# mp28164-buck-boost-flashlight-driver-tes.net
KiCad netlist of a schematic drawn in EAGLE
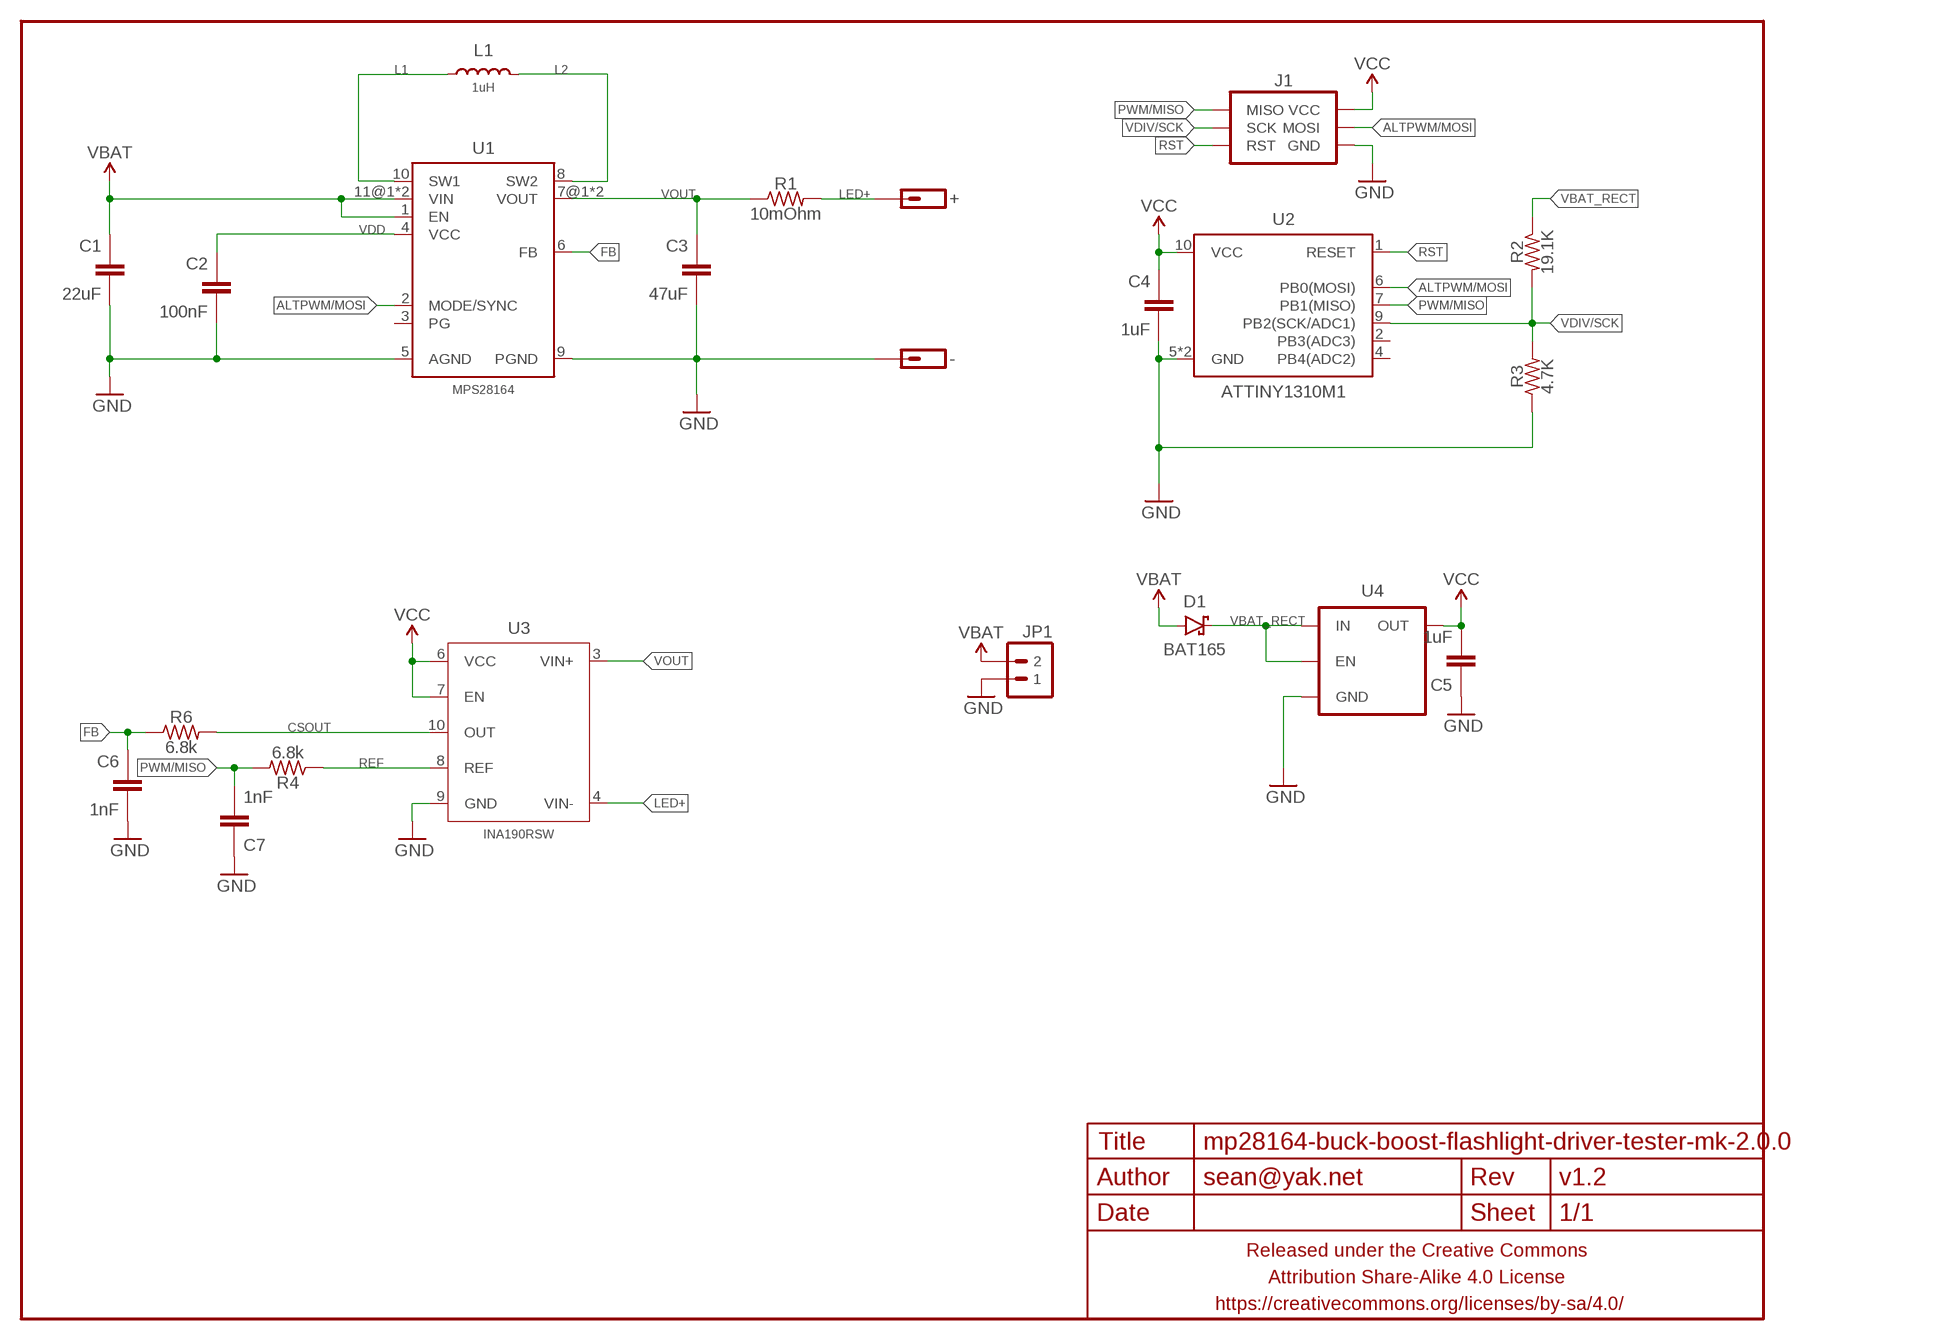
[diagram p0: schematic, sheet 1]

(export (version "E")
  (design (tool "Eeschema 10.0.6"))
  (components
    (comp (ref "+")
      (value "M01PTH-1.2MM-NS")
      (footprint "eagle-import:1X01-1.2MM-NS")
      (libsource (lib "eagle-import") (part "M01PTH-1.2MM-NS"))
    )
    (comp (ref "-")
      (value "M01PTH-1.2MM-NS")
      (footprint "eagle-import:1X01-1.2MM-NS")
      (libsource (lib "eagle-import") (part "M01PTH-1.2MM-NS"))
    )
    (comp (ref "C1")
      (value "22uF")
      (footprint "eagle-import:C1206")
      (libsource (lib "eagle-import") (part "CAPACITOR-CERAMICC1206"))
    )
    (comp (ref "C2")
      (value "100nF")
      (footprint "eagle-import:C0402")
      (libsource (lib "eagle-import") (part "CAPACITOR-CERAMICC0402"))
    )
    (comp (ref "C3")
      (value "47uF")
      (footprint "eagle-import:C1206")
      (libsource (lib "eagle-import") (part "CAPACITOR-CERAMICC1206"))
    )
    (comp (ref "C4")
      (value "1uF")
      (footprint "eagle-import:C0402")
      (libsource (lib "eagle-import") (part "CAPACITOR-CERAMICC0402"))
    )
    (comp (ref "C5")
      (value "1uF")
      (footprint "eagle-import:C0402")
      (libsource (lib "eagle-import") (part "CAPACITOR-CERAMICC0402"))
    )
    (comp (ref "C6")
      (value "1nF")
      (footprint "eagle-import:C0402")
      (libsource (lib "eagle-import") (part "CAPACITOR-CERAMICC0402"))
    )
    (comp (ref "C7")
      (value "1nF")
      (footprint "eagle-import:C0402")
      (libsource (lib "eagle-import") (part "CAPACITOR-CERAMICC0402"))
    )
    (comp (ref "D1")
      (value "BAT165")
      (footprint "eagle-import:SOD323-SCHOTTKY")
      (libsource (lib "eagle-import") (part "DIODE-SCHOTTKYSOD323"))
    )
    (comp (ref "FRAME1")
      (value "FRAME-LETTERNO_PACKAGE")
      (footprint "eagle-import:DUMMY")
      (fields
        (field (name "DESIGNER") "sean@yak.net")
        (field (name "VERSION") "v1.2")
        (field (name "DESIGNER_1") "sean@yak.net")
        (field (name "VERSION_1") "v1.2")
      )
      (libsource (lib "eagle-import") (part "FRAME-LETTERNO_PACKAGE"))
    )
    (comp (ref "J1")
      (value "AVR_SPI_PRG_6PTH")
      (footprint "eagle-import:2X3")
      (libsource (lib "eagle-import") (part "AVR_SPI_PRG_6PTH"))
    )
    (comp (ref "JP1")
      (value "M02PTH")
      (footprint "eagle-import:1X02")
      (libsource (lib "eagle-import") (part "M02PTH"))
    )
    (comp (ref "L1")
      (value "1uH")
      (footprint "eagle-import:XAL60XX")
      (libsource (lib "eagle-import") (part "INDUCTORXAL60XX"))
    )
    (comp (ref "R1")
      (value "10mOhm")
      (footprint "eagle-import:R1206")
      (libsource (lib "eagle-import") (part "RESISTORR1206"))
    )
    (comp (ref "R2")
      (value "19.1K")
      (footprint "eagle-import:R0402")
      (libsource (lib "eagle-import") (part "RESISTORR0402"))
    )
    (comp (ref "R3")
      (value "4.7K")
      (footprint "eagle-import:R0402")
      (libsource (lib "eagle-import") (part "RESISTORR0402"))
    )
    (comp (ref "R4")
      (value "6.8k")
      (footprint "eagle-import:R0402")
      (libsource (lib "eagle-import") (part "RESISTORR0402"))
    )
    (comp (ref "R6")
      (value "6.8k")
      (footprint "eagle-import:R0402")
      (libsource (lib "eagle-import") (part "RESISTORR0402"))
    )
    (comp (ref "U1")
      (value "MPS28164")
      (footprint "eagle-import:MPS28164")
      (libsource (lib "eagle-import") (part "MPS28164"))
    )
    (comp (ref "U2")
      (value "ATTINY1310M1")
      (footprint "eagle-import:QFN10(2X5)")
      (libsource (lib "eagle-import") (part "ATTINY1310M1"))
    )
    (comp (ref "U3")
      (value "INA190RSW")
      (footprint "eagle-import:UQFN-10")
      (libsource (lib "eagle-import") (part "INA190RSW"))
    )
    (comp (ref "U4")
      (value "V_REG_ENTLV700")
      (footprint "eagle-import:SC70")
      (libsource (lib "eagle-import") (part "V_REG_ENTLV700"))
    )
  )
  (nets
    (net (code "1") (name "/CSOUT") (class "Default")
      (node (ref "R6") (pin "2") (pinfunction "2_2") (pintype "passive"))
      (node (ref "U3") (pin "10") (pinfunction "OUT_10") (pintype "bidirectional"))
    )
    (net (code "2") (name "/L1") (class "Default")
      (node (ref "L1") (pin "P$1") (pinfunction "1_P$1") (pintype "passive"))
      (node (ref "U1") (pin "10") (pinfunction "SW1_10") (pintype "bidirectional"))
    )
    (net (code "3") (name "/L2") (class "Default")
      (node (ref "L1") (pin "P$2") (pinfunction "2_P$2") (pintype "passive"))
      (node (ref "U1") (pin "8") (pinfunction "SW2_8") (pintype "bidirectional"))
    )
    (net (code "4") (name "/REF") (class "Default")
      (node (ref "R4") (pin "1") (pinfunction "1_1") (pintype "passive"))
      (node (ref "U3") (pin "8") (pinfunction "REF_8") (pintype "bidirectional"))
    )
    (net (code "5") (name "/VDD") (class "Default")
      (node (ref "C2") (pin "1") (pinfunction "1_1") (pintype "passive"))
      (node (ref "U1") (pin "4") (pinfunction "VCC_4") (pintype "bidirectional"))
    )
    (net (code "6") (name "ALTPWM{slash}MOSI") (class "Default")
      (node (ref "J1") (pin "4") (pinfunction "MOSI_4") (pintype "passive"))
      (node (ref "U1") (pin "2") (pinfunction "MODE/SYNC_2") (pintype "bidirectional"))
      (node (ref "U2") (pin "6") (pinfunction "PB0(MOSI)_6") (pintype "bidirectional"))
    )
    (net (code "7") (name "FB") (class "Default")
      (node (ref "C6") (pin "1") (pinfunction "1_1") (pintype "passive"))
      (node (ref "R6") (pin "1") (pinfunction "1_1") (pintype "passive"))
      (node (ref "U1") (pin "6") (pinfunction "FB_6") (pintype "bidirectional"))
    )
    (net (code "8") (name "GND") (class "Default")
      (node (ref "-") (pin "P$1") (pinfunction "1_P$1") (pintype "passive"))
      (node (ref "C1") (pin "2") (pinfunction "2_2") (pintype "passive"))
      (node (ref "C2") (pin "2") (pinfunction "2_2") (pintype "passive"))
      (node (ref "C3") (pin "2") (pinfunction "2_2") (pintype "passive"))
      (node (ref "C4") (pin "2") (pinfunction "2_2") (pintype "passive"))
      (node (ref "C5") (pin "1") (pinfunction "1_1") (pintype "passive"))
      (node (ref "C6") (pin "2") (pinfunction "2_2") (pintype "passive"))
      (node (ref "C7") (pin "1") (pinfunction "1_1") (pintype "passive"))
      (node (ref "J1") (pin "6") (pinfunction "GND_6") (pintype "passive"))
      (node (ref "JP1") (pin "1") (pinfunction "1_1") (pintype "passive"))
      (node (ref "R3") (pin "1") (pinfunction "1_1") (pintype "passive"))
      (node (ref "U1") (pin "5") (pinfunction "AGND_5") (pintype "bidirectional"))
      (node (ref "U1") (pin "9") (pinfunction "PGND_9") (pintype "bidirectional"))
      (node (ref "U2") (pin "5") (pinfunction "GND_5") (pintype "bidirectional"))
      (node (ref "U2") (pin "PAD") (pinfunction "GND_PAD") (pintype "bidirectional"))
      (node (ref "U3") (pin "9") (pinfunction "GND_9") (pintype "bidirectional"))
      (node (ref "U4") (pin "2") (pinfunction "GND_2") (pintype "input"))
    )
    (net (code "9") (name "LED+") (class "Default")
      (node (ref "+") (pin "P$1") (pinfunction "1_P$1") (pintype "passive"))
      (node (ref "R1") (pin "2") (pinfunction "2_2") (pintype "passive"))
      (node (ref "U3") (pin "4") (pinfunction "VIN-_4") (pintype "bidirectional"))
    )
    (net (code "10") (name "PWM{slash}MISO") (class "Default")
      (node (ref "C7") (pin "2") (pinfunction "2_2") (pintype "passive"))
      (node (ref "J1") (pin "1") (pinfunction "MISO_1") (pintype "passive"))
      (node (ref "R4") (pin "2") (pinfunction "2_2") (pintype "passive"))
      (node (ref "U2") (pin "7") (pinfunction "PB1(MISO)_7") (pintype "bidirectional"))
    )
    (net (code "11") (name "RST") (class "Default")
      (node (ref "J1") (pin "5") (pinfunction "RST_5") (pintype "passive"))
      (node (ref "U2") (pin "1") (pinfunction "RESET_1") (pintype "bidirectional"))
    )
    (net (code "12") (name "VBAT") (class "Default")
      (node (ref "C1") (pin "1") (pinfunction "1_1") (pintype "passive"))
      (node (ref "D1") (pin "A") (pinfunction "A_A") (pintype "passive"))
      (node (ref "JP1") (pin "2") (pinfunction "2_2") (pintype "passive"))
      (node (ref "U1") (pin "1") (pinfunction "EN_1") (pintype "bidirectional"))
      (node (ref "U1") (pin "11@1") (pinfunction "VIN_11@1") (pintype "bidirectional"))
      (node (ref "U1") (pin "11@2") (pinfunction "VIN_11@2") (pintype "bidirectional"))
    )
    (net (code "13") (name "VBAT_RECT") (class "Default")
      (node (ref "D1") (pin "C") (pinfunction "C_C") (pintype "passive"))
      (node (ref "R2") (pin "1") (pinfunction "1_1") (pintype "passive"))
      (node (ref "U4") (pin "1") (pinfunction "IN_1") (pintype "input"))
      (node (ref "U4") (pin "3") (pinfunction "EN_3") (pintype "input"))
    )
    (net (code "14") (name "VCC") (class "Default")
      (node (ref "C4") (pin "1") (pinfunction "1_1") (pintype "passive"))
      (node (ref "C5") (pin "2") (pinfunction "2_2") (pintype "passive"))
      (node (ref "J1") (pin "2") (pinfunction "VCC_2") (pintype "passive"))
      (node (ref "U2") (pin "10") (pinfunction "VCC_10") (pintype "bidirectional"))
      (node (ref "U3") (pin "6") (pinfunction "VCC_6") (pintype "bidirectional"))
      (node (ref "U3") (pin "7") (pinfunction "EN_7") (pintype "bidirectional"))
      (node (ref "U4") (pin "5") (pinfunction "OUT_5") (pintype "passive"))
    )
    (net (code "15") (name "VDIV{slash}SCK") (class "Default")
      (node (ref "J1") (pin "3") (pinfunction "SCK_3") (pintype "passive"))
      (node (ref "R2") (pin "2") (pinfunction "2_2") (pintype "passive"))
      (node (ref "R3") (pin "2") (pinfunction "2_2") (pintype "passive"))
      (node (ref "U2") (pin "9") (pinfunction "PB2(SCK/ADC1)_9") (pintype "bidirectional"))
    )
    (net (code "16") (name "VOUT") (class "Default")
      (node (ref "C3") (pin "1") (pinfunction "1_1") (pintype "passive"))
      (node (ref "R1") (pin "1") (pinfunction "1_1") (pintype "passive"))
      (node (ref "U1") (pin "7@1") (pinfunction "VOUT_7@1") (pintype "bidirectional"))
      (node (ref "U1") (pin "7@2") (pinfunction "VOUT_7@2") (pintype "bidirectional"))
      (node (ref "U3") (pin "3") (pinfunction "VIN+_3") (pintype "bidirectional"))
    )
    (net (code "17") (name "unconnected-(U1-PG-Pad3)") (class "Default")
      (node (ref "U1") (pin "3") (pinfunction "PG_3") (pintype "bidirectional"))
    )
    (net (code "18") (name "unconnected-(U2-PB3(ADC3)-Pad2)") (class "Default")
      (node (ref "U2") (pin "2") (pinfunction "PB3(ADC3)_2") (pintype "bidirectional"))
    )
    (net (code "19") (name "unconnected-(U2-PB4(ADC2)-Pad4)") (class "Default")
      (node (ref "U2") (pin "4") (pinfunction "PB4(ADC2)_4") (pintype "bidirectional"))
    )
  )
)
